# smartcar_shield_cutouts.net
KiCad netlist of a schematic drawn in EAGLE
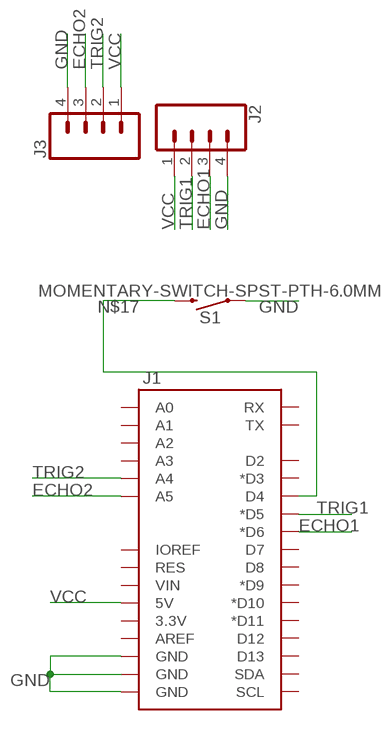
[diagram p0: schematic, sheet 1]

(export (version "E")
  (design (tool "Eeschema 10.0.6"))
  (components
    (comp (ref "J1")
      (value "ARDUINO_R3_SHIELDUNO_R3_SHIELD_LOCK")
      (footprint "eagle-import:UNO_R3_SHIELD_LOCK")
      (libsource (lib "eagle-import") (part "ARDUINO_R3_SHIELDUNO_R3_SHIELD_LOCK"))
    )
    (comp (ref "J2")
      (value "CONN_04")
      (footprint "eagle-import:1X04")
      (libsource (lib "eagle-import") (part "CONN_04"))
    )
    (comp (ref "J3")
      (value "CONN_04")
      (footprint "eagle-import:1X04")
      (libsource (lib "eagle-import") (part "CONN_04"))
    )
    (comp (ref "S1")
      (value "MOMENTARY-SWITCH-SPST-PTH-6.0MM")
      (footprint "eagle-import:TACTILE_SWITCH_PTH_6.0MM")
      (libsource (lib "eagle-import") (part "MOMENTARY-SWITCH-SPST-PTH-6.0MM"))
    )
  )
  (nets
    (net (code "1") (name "/ECHO1") (class "Default")
      (node (ref "J1") (pin "D6") (pinfunction "*D6_D6") (pintype "bidirectional"))
      (node (ref "J2") (pin "3") (pinfunction "3_3") (pintype "passive"))
    )
    (net (code "2") (name "/ECHO2") (class "Default")
      (node (ref "J1") (pin "A5") (pinfunction "A5_A5") (pintype "bidirectional"))
      (node (ref "J3") (pin "3") (pinfunction "3_3") (pintype "passive"))
    )
    (net (code "3") (name "/GND") (class "Default")
      (node (ref "J1") (pin "GND@0") (pinfunction "GND_GND@0") (pintype "bidirectional"))
      (node (ref "J1") (pin "GND@1") (pinfunction "GND_GND@1") (pintype "bidirectional"))
      (node (ref "J1") (pin "GND@2") (pinfunction "GND_GND@2") (pintype "bidirectional"))
      (node (ref "J2") (pin "4") (pinfunction "4_4") (pintype "passive"))
      (node (ref "J3") (pin "4") (pinfunction "4_4") (pintype "passive"))
      (node (ref "S1") (pin "1") (pinfunction "1_1") (pintype "passive"))
    )
    (net (code "4") (name "/N$17") (class "Default")
      (node (ref "J1") (pin "D4") (pinfunction "D4_D4") (pintype "bidirectional"))
      (node (ref "S1") (pin "3") (pinfunction "2_3") (pintype "passive"))
    )
    (net (code "5") (name "/TRIG1") (class "Default")
      (node (ref "J1") (pin "D5") (pinfunction "*D5_D5") (pintype "bidirectional"))
      (node (ref "J2") (pin "2") (pinfunction "2_2") (pintype "passive"))
    )
    (net (code "6") (name "/TRIG2") (class "Default")
      (node (ref "J1") (pin "A4") (pinfunction "A4_A4") (pintype "bidirectional"))
      (node (ref "J3") (pin "2") (pinfunction "2_2") (pintype "passive"))
    )
    (net (code "7") (name "/VCC") (class "Default")
      (node (ref "J1") (pin "5V") (pinfunction "5V_5V") (pintype "bidirectional"))
      (node (ref "J2") (pin "1") (pinfunction "1_1") (pintype "passive"))
      (node (ref "J3") (pin "1") (pinfunction "1_1") (pintype "passive"))
    )
    (net (code "8") (name "unconnected-(J1-*D3-PadD3)") (class "Default")
      (node (ref "J1") (pin "D3") (pinfunction "*D3_D3") (pintype "bidirectional"))
    )
    (net (code "9") (name "unconnected-(J1-*D9-PadD9)") (class "Default")
      (node (ref "J1") (pin "D9") (pinfunction "*D9_D9") (pintype "bidirectional"))
    )
    (net (code "10") (name "unconnected-(J1-*D10-PadD10)") (class "Default")
      (node (ref "J1") (pin "D10") (pinfunction "*D10_D10") (pintype "bidirectional"))
    )
    (net (code "11") (name "unconnected-(J1-*D11-PadD11)") (class "Default")
      (node (ref "J1") (pin "D11") (pinfunction "*D11_D11") (pintype "bidirectional"))
    )
    (net (code "12") (name "unconnected-(J1-Pad3.3V)") (class "Default")
      (node (ref "J1") (pin "3.3V") (pinfunction "3.3V_3.3V") (pintype "bidirectional"))
    )
    (net (code "13") (name "unconnected-(J1-PadA0)") (class "Default")
      (node (ref "J1") (pin "A0") (pinfunction "A0_A0") (pintype "bidirectional"))
    )
    (net (code "14") (name "unconnected-(J1-PadA1)") (class "Default")
      (node (ref "J1") (pin "A1") (pinfunction "A1_A1") (pintype "bidirectional"))
    )
    (net (code "15") (name "unconnected-(J1-PadA2)") (class "Default")
      (node (ref "J1") (pin "A2") (pinfunction "A2_A2") (pintype "bidirectional"))
    )
    (net (code "16") (name "unconnected-(J1-PadA3)") (class "Default")
      (node (ref "J1") (pin "A3") (pinfunction "A3_A3") (pintype "bidirectional"))
    )
    (net (code "17") (name "unconnected-(J1-PadAREF)") (class "Default")
      (node (ref "J1") (pin "AREF") (pinfunction "AREF_AREF") (pintype "bidirectional"))
    )
    (net (code "18") (name "unconnected-(J1-PadD2)") (class "Default")
      (node (ref "J1") (pin "D2") (pinfunction "D2_D2") (pintype "bidirectional"))
    )
    (net (code "19") (name "unconnected-(J1-PadD7)") (class "Default")
      (node (ref "J1") (pin "D7") (pinfunction "D7_D7") (pintype "bidirectional"))
    )
    (net (code "20") (name "unconnected-(J1-PadD8)") (class "Default")
      (node (ref "J1") (pin "D8") (pinfunction "D8_D8") (pintype "bidirectional"))
    )
    (net (code "21") (name "unconnected-(J1-PadD12)") (class "Default")
      (node (ref "J1") (pin "D12") (pinfunction "D12_D12") (pintype "bidirectional"))
    )
    (net (code "22") (name "unconnected-(J1-PadD13)") (class "Default")
      (node (ref "J1") (pin "D13") (pinfunction "D13_D13") (pintype "bidirectional"))
    )
    (net (code "23") (name "unconnected-(J1-PadIOREF)") (class "Default")
      (node (ref "J1") (pin "IOREF") (pinfunction "IOREF_IOREF") (pintype "bidirectional"))
    )
    (net (code "24") (name "unconnected-(J1-PadRES)") (class "Default")
      (node (ref "J1") (pin "RES") (pinfunction "RES_RES") (pintype "bidirectional"))
    )
    (net (code "25") (name "unconnected-(J1-PadRX)") (class "Default")
      (node (ref "J1") (pin "RX") (pinfunction "RX_RX") (pintype "bidirectional"))
    )
    (net (code "26") (name "unconnected-(J1-PadSCL)") (class "Default")
      (node (ref "J1") (pin "SCL") (pinfunction "SCL_SCL") (pintype "bidirectional"))
    )
    (net (code "27") (name "unconnected-(J1-PadSDA)") (class "Default")
      (node (ref "J1") (pin "SDA") (pinfunction "SDA_SDA") (pintype "bidirectional"))
    )
    (net (code "28") (name "unconnected-(J1-PadTX)") (class "Default")
      (node (ref "J1") (pin "TX") (pinfunction "TX_TX") (pintype "bidirectional"))
    )
    (net (code "29") (name "unconnected-(J1-PadVIN)") (class "Default")
      (node (ref "J1") (pin "VIN") (pinfunction "VIN_VIN") (pintype "bidirectional"))
    )
  )
)
